# bone_capes.net
KiCad netlist of a schematic drawn in Altium Designer
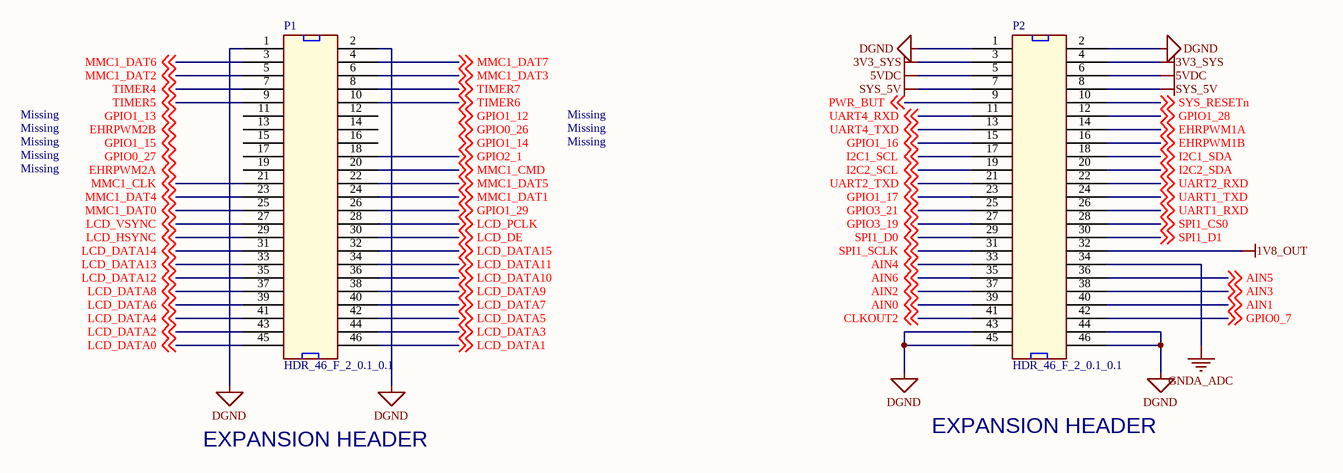
[diagram p0: bone_capes.SchDoc]

(export (version "E")
  (design (tool "Eeschema 10.0.6"))
  (components
    (comp (ref "P1")
      (value "HDR_46_F_2_0.1_0.1")
      (footprint "DIP46")
      (description "NN HEADER FMAL 46PS.1\" DL GOLD")
      (fields (field (name "MFR") "major league electronics"))
      (libsource (lib "am335x-base") (part "HDR_46_F_2_0.1_0.1"))
    )
    (comp (ref "P2")
      (value "HDR_46_F_2_0.1_0.1")
      (footprint "DIP46")
      (description "NN HEADER FMAL 46PS.1\" DL GOLD")
      (fields (field (name "MFR") "major league electronics"))
      (libsource (lib "am335x-base") (part "HDR_46_F_2_0.1_0.1"))
    )
  )
  (nets
    (net (code "1") (name "1V8_OUT") (class "Default")
      (node (ref "P2") (pin "32") (pinfunction "41_32") (pintype "passive"))
    )
    (net (code "2") (name "3V3_SYS") (class "Default")
      (node (ref "P2") (pin "3") (pinfunction "2_3") (pintype "passive"))
      (node (ref "P2") (pin "4") (pinfunction "27_4") (pintype "passive"))
    )
    (net (code "3") (name "5VDC") (class "Default")
      (node (ref "P2") (pin "5") (pinfunction "3_5") (pintype "passive"))
      (node (ref "P2") (pin "6") (pinfunction "28_6") (pintype "passive"))
    )
    (net (code "4") (name "AIN0") (class "Default")
      (node (ref "P2") (pin "39") (pinfunction "20_39") (pintype "passive"))
    )
    (net (code "5") (name "AIN1") (class "Default")
      (node (ref "P2") (pin "40") (pinfunction "45_40") (pintype "passive"))
    )
    (net (code "6") (name "AIN2") (class "Default")
      (node (ref "P2") (pin "37") (pinfunction "19_37") (pintype "passive"))
    )
    (net (code "7") (name "AIN3") (class "Default")
      (node (ref "P2") (pin "38") (pinfunction "44_38") (pintype "passive"))
    )
    (net (code "8") (name "AIN4") (class "Default")
      (node (ref "P2") (pin "33") (pinfunction "17_33") (pintype "passive"))
    )
    (net (code "9") (name "AIN5") (class "Default")
      (node (ref "P2") (pin "36") (pinfunction "43_36") (pintype "passive"))
    )
    (net (code "10") (name "AIN6") (class "Default")
      (node (ref "P2") (pin "35") (pinfunction "18_35") (pintype "passive"))
    )
    (net (code "11") (name "CLKOUT2") (class "Default")
      (node (ref "P2") (pin "41") (pinfunction "21_41") (pintype "passive"))
    )
    (net (code "12") (name "DGND") (class "Default")
      (node (ref "P1") (pin "1") (pinfunction "1_1") (pintype "passive"))
      (node (ref "P1") (pin "2") (pinfunction "26_2") (pintype "passive"))
      (node (ref "P2") (pin "1") (pinfunction "1_1") (pintype "passive"))
      (node (ref "P2") (pin "2") (pinfunction "26_2") (pintype "passive"))
      (node (ref "P2") (pin "43") (pinfunction "22_43") (pintype "passive"))
      (node (ref "P2") (pin "44") (pinfunction "47_44") (pintype "passive"))
      (node (ref "P2") (pin "45") (pinfunction "23_45") (pintype "passive"))
      (node (ref "P2") (pin "46") (pinfunction "48_46") (pintype "passive"))
    )
    (net (code "13") (name "EHRPWM1A") (class "Default")
      (node (ref "P2") (pin "14") (pinfunction "32_14") (pintype "passive"))
    )
    (net (code "14") (name "EHRPWM1B") (class "Default")
      (node (ref "P2") (pin "16") (pinfunction "33_16") (pintype "passive"))
    )
    (net (code "17") (name "GNDA_ADC") (class "Default")
      (node (ref "P2") (pin "34") (pinfunction "42_34") (pintype "passive"))
    )
    (net (code "18") (name "GPIO0_7") (class "Default")
      (node (ref "P2") (pin "42") (pinfunction "46_42") (pintype "passive"))
    )
    (net (code "25") (name "GPIO1_16") (class "Default")
      (node (ref "P2") (pin "15") (pinfunction "8_15") (pintype "passive"))
    )
    (net (code "26") (name "GPIO1_17") (class "Default")
      (node (ref "P2") (pin "23") (pinfunction "12_23") (pintype "passive"))
    )
    (net (code "27") (name "GPIO1_28") (class "Default")
      (node (ref "P2") (pin "12") (pinfunction "31_12") (pintype "passive"))
    )
    (net (code "28") (name "GPIO1_29") (class "Default")
      (node (ref "P1") (pin "26") (pinfunction "38_26") (pintype "passive"))
    )
    (net (code "29") (name "GPIO2_1") (class "Default")
      (node (ref "P1") (pin "18") (pinfunction "34_18") (pintype "passive"))
    )
    (net (code "30") (name "GPIO3_19") (class "Default")
      (node (ref "P2") (pin "27") (pinfunction "14_27") (pintype "passive"))
    )
    (net (code "31") (name "GPIO3_21") (class "Default")
      (node (ref "P2") (pin "25") (pinfunction "13_25") (pintype "passive"))
    )
    (net (code "32") (name "I2C1_SCL") (class "Default")
      (node (ref "P2") (pin "17") (pinfunction "9_17") (pintype "passive"))
    )
    (net (code "33") (name "I2C1_SDA") (class "Default")
      (node (ref "P2") (pin "18") (pinfunction "34_18") (pintype "passive"))
    )
    (net (code "34") (name "I2C2_SCL") (class "Default")
      (node (ref "P2") (pin "19") (pinfunction "10_19") (pintype "passive"))
    )
    (net (code "35") (name "I2C2_SDA") (class "Default")
      (node (ref "P2") (pin "20") (pinfunction "35_20") (pintype "passive"))
    )
    (net (code "36") (name "LCD_DATA0") (class "Default")
      (node (ref "P1") (pin "45") (pinfunction "23_45") (pintype "passive"))
    )
    (net (code "37") (name "LCD_DATA1") (class "Default")
      (node (ref "P1") (pin "46") (pinfunction "48_46") (pintype "passive"))
    )
    (net (code "38") (name "LCD_DATA2") (class "Default")
      (node (ref "P1") (pin "43") (pinfunction "22_43") (pintype "passive"))
    )
    (net (code "39") (name "LCD_DATA3") (class "Default")
      (node (ref "P1") (pin "44") (pinfunction "47_44") (pintype "passive"))
    )
    (net (code "40") (name "LCD_DATA4") (class "Default")
      (node (ref "P1") (pin "41") (pinfunction "21_41") (pintype "passive"))
    )
    (net (code "41") (name "LCD_DATA5") (class "Default")
      (node (ref "P1") (pin "42") (pinfunction "46_42") (pintype "passive"))
    )
    (net (code "42") (name "LCD_DATA6") (class "Default")
      (node (ref "P1") (pin "39") (pinfunction "20_39") (pintype "passive"))
    )
    (net (code "43") (name "LCD_DATA7") (class "Default")
      (node (ref "P1") (pin "40") (pinfunction "45_40") (pintype "passive"))
    )
    (net (code "44") (name "LCD_DATA8") (class "Default")
      (node (ref "P1") (pin "37") (pinfunction "19_37") (pintype "passive"))
    )
    (net (code "45") (name "LCD_DATA9") (class "Default")
      (node (ref "P1") (pin "38") (pinfunction "44_38") (pintype "passive"))
    )
    (net (code "46") (name "LCD_DATA10") (class "Default")
      (node (ref "P1") (pin "36") (pinfunction "43_36") (pintype "passive"))
    )
    (net (code "47") (name "LCD_DATA11") (class "Default")
      (node (ref "P1") (pin "34") (pinfunction "42_34") (pintype "passive"))
    )
    (net (code "48") (name "LCD_DATA12") (class "Default")
      (node (ref "P1") (pin "35") (pinfunction "18_35") (pintype "passive"))
    )
    (net (code "49") (name "LCD_DATA13") (class "Default")
      (node (ref "P1") (pin "33") (pinfunction "17_33") (pintype "passive"))
    )
    (net (code "50") (name "LCD_DATA14") (class "Default")
      (node (ref "P1") (pin "31") (pinfunction "16_31") (pintype "passive"))
    )
    (net (code "51") (name "LCD_DATA15") (class "Default")
      (node (ref "P1") (pin "32") (pinfunction "41_32") (pintype "passive"))
    )
    (net (code "52") (name "LCD_DE") (class "Default")
      (node (ref "P1") (pin "30") (pinfunction "40_30") (pintype "passive"))
    )
    (net (code "53") (name "LCD_HSYNC") (class "Default")
      (node (ref "P1") (pin "29") (pinfunction "15_29") (pintype "passive"))
    )
    (net (code "54") (name "LCD_PCLK") (class "Default")
      (node (ref "P1") (pin "28") (pinfunction "39_28") (pintype "passive"))
    )
    (net (code "55") (name "LCD_VSYNC") (class "Default")
      (node (ref "P1") (pin "27") (pinfunction "14_27") (pintype "passive"))
    )
    (net (code "56") (name "MMC1_CLK") (class "Default")
      (node (ref "P1") (pin "21") (pinfunction "11_21") (pintype "passive"))
    )
    (net (code "57") (name "MMC1_CMD") (class "Default")
      (node (ref "P1") (pin "20") (pinfunction "35_20") (pintype "passive"))
    )
    (net (code "58") (name "MMC1_DAT0") (class "Default")
      (node (ref "P1") (pin "25") (pinfunction "13_25") (pintype "passive"))
    )
    (net (code "59") (name "MMC1_DAT1") (class "Default")
      (node (ref "P1") (pin "24") (pinfunction "37_24") (pintype "passive"))
    )
    (net (code "60") (name "MMC1_DAT2") (class "Default")
      (node (ref "P1") (pin "5") (pinfunction "3_5") (pintype "passive"))
    )
    (net (code "61") (name "MMC1_DAT3") (class "Default")
      (node (ref "P1") (pin "6") (pinfunction "28_6") (pintype "passive"))
    )
    (net (code "62") (name "MMC1_DAT4") (class "Default")
      (node (ref "P1") (pin "23") (pinfunction "12_23") (pintype "passive"))
    )
    (net (code "63") (name "MMC1_DAT5") (class "Default")
      (node (ref "P1") (pin "22") (pinfunction "36_22") (pintype "passive"))
    )
    (net (code "64") (name "MMC1_DAT6") (class "Default")
      (node (ref "P1") (pin "3") (pinfunction "2_3") (pintype "passive"))
    )
    (net (code "65") (name "MMC1_DAT7") (class "Default")
      (node (ref "P1") (pin "4") (pinfunction "27_4") (pintype "passive"))
    )
    (net (code "66") (name "PWR_BUT") (class "Default")
      (node (ref "P2") (pin "9") (pinfunction "5_9") (pintype "passive"))
    )
    (net (code "67") (name "SPI1_CS0") (class "Default")
      (node (ref "P2") (pin "28") (pinfunction "39_28") (pintype "passive"))
    )
    (net (code "68") (name "SPI1_D0") (class "Default")
      (node (ref "P2") (pin "29") (pinfunction "15_29") (pintype "passive"))
    )
    (net (code "69") (name "SPI1_D1") (class "Default")
      (node (ref "P2") (pin "30") (pinfunction "40_30") (pintype "passive"))
    )
    (net (code "70") (name "SPI1_SCLK") (class "Default")
      (node (ref "P2") (pin "31") (pinfunction "16_31") (pintype "passive"))
    )
    (net (code "71") (name "SYS_5V") (class "Default")
      (node (ref "P2") (pin "7") (pinfunction "4_7") (pintype "passive"))
      (node (ref "P2") (pin "8") (pinfunction "29_8") (pintype "passive"))
    )
    (net (code "72") (name "SYS_RESETn") (class "Default")
      (node (ref "P2") (pin "10") (pinfunction "30_10") (pintype "passive"))
    )
    (net (code "73") (name "TIMER4") (class "Default")
      (node (ref "P1") (pin "7") (pinfunction "4_7") (pintype "passive"))
    )
    (net (code "74") (name "TIMER5") (class "Default")
      (node (ref "P1") (pin "9") (pinfunction "5_9") (pintype "passive"))
    )
    (net (code "75") (name "TIMER6") (class "Default")
      (node (ref "P1") (pin "10") (pinfunction "30_10") (pintype "passive"))
    )
    (net (code "76") (name "TIMER7") (class "Default")
      (node (ref "P1") (pin "8") (pinfunction "29_8") (pintype "passive"))
    )
    (net (code "77") (name "UART1_RXD") (class "Default")
      (node (ref "P2") (pin "26") (pinfunction "38_26") (pintype "passive"))
    )
    (net (code "78") (name "UART1_TXD") (class "Default")
      (node (ref "P2") (pin "24") (pinfunction "37_24") (pintype "passive"))
    )
    (net (code "79") (name "UART2_RXD") (class "Default")
      (node (ref "P2") (pin "22") (pinfunction "36_22") (pintype "passive"))
    )
    (net (code "80") (name "UART2_TXD") (class "Default")
      (node (ref "P2") (pin "21") (pinfunction "11_21") (pintype "passive"))
    )
    (net (code "81") (name "UART4_RXD") (class "Default")
      (node (ref "P2") (pin "11") (pinfunction "6_11") (pintype "passive"))
    )
    (net (code "82") (name "UART4_TXD") (class "Default")
      (node (ref "P2") (pin "13") (pinfunction "7_13") (pintype "passive"))
    )
    (net (code "83") (name "unconnected-(P1-6-Pad11)") (class "Default")
      (node (ref "P1") (pin "11") (pinfunction "6_11") (pintype "passive"))
    )
    (net (code "84") (name "unconnected-(P1-7-Pad13)") (class "Default")
      (node (ref "P1") (pin "13") (pinfunction "7_13") (pintype "passive"))
    )
    (net (code "85") (name "unconnected-(P1-8-Pad15)") (class "Default")
      (node (ref "P1") (pin "15") (pinfunction "8_15") (pintype "passive"))
    )
    (net (code "86") (name "unconnected-(P1-9-Pad17)") (class "Default")
      (node (ref "P1") (pin "17") (pinfunction "9_17") (pintype "passive"))
    )
    (net (code "87") (name "unconnected-(P1-10-Pad19)") (class "Default")
      (node (ref "P1") (pin "19") (pinfunction "10_19") (pintype "passive"))
    )
    (net (code "88") (name "unconnected-(P1-31-Pad12)") (class "Default")
      (node (ref "P1") (pin "12") (pinfunction "31_12") (pintype "passive"))
    )
    (net (code "89") (name "unconnected-(P1-32-Pad14)") (class "Default")
      (node (ref "P1") (pin "14") (pinfunction "32_14") (pintype "passive"))
    )
    (net (code "90") (name "unconnected-(P1-33-Pad16)") (class "Default")
      (node (ref "P1") (pin "16") (pinfunction "33_16") (pintype "passive"))
    )
  )
)
